# wheel_encoder.net
KiCad netlist of a schematic drawn in EAGLE
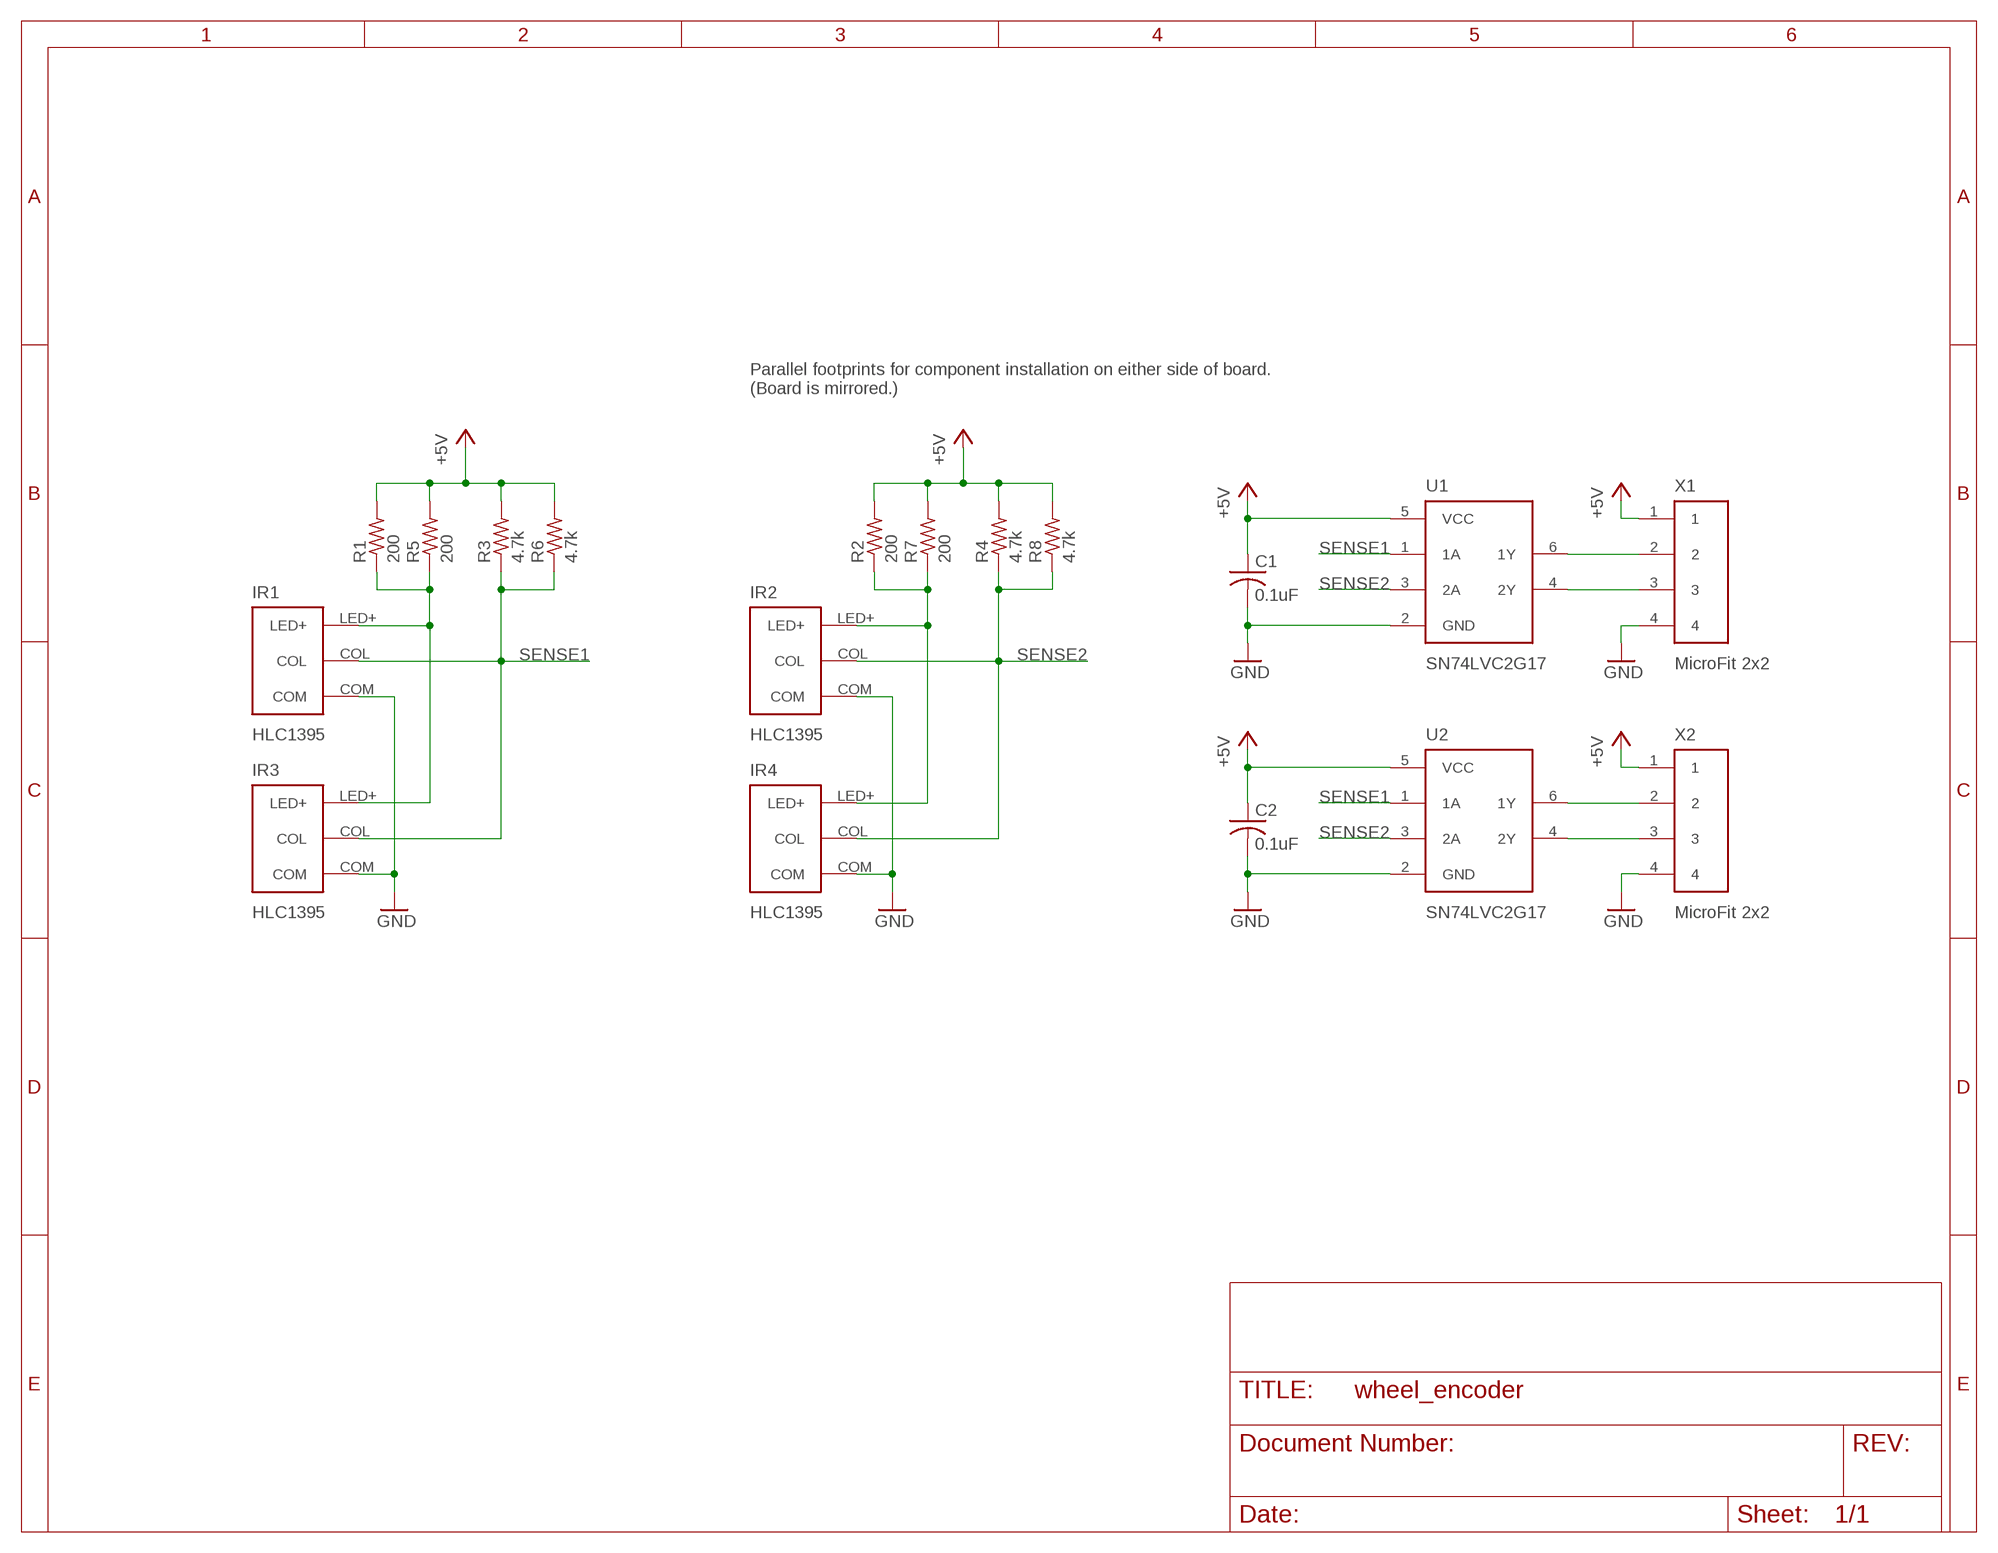
[diagram p0: schematic, sheet 1]

(export (version "E")
  (design (tool "Eeschema 10.0.6"))
  (components
    (comp (ref "C1")
      (value "0.1uF")
      (footprint "eagle-import:C0603")
      (libsource (lib "eagle-import") (part "C-USC0603"))
    )
    (comp (ref "C2")
      (value "0.1uF")
      (footprint "eagle-import:C0603")
      (libsource (lib "eagle-import") (part "C-USC0603"))
    )
    (comp (ref "IR1")
      (value "HLC1395")
      (footprint "eagle-import:HLC1395")
      (libsource (lib "eagle-import") (part "HLC1395"))
    )
    (comp (ref "IR2")
      (value "HLC1395")
      (footprint "eagle-import:HLC1395")
      (libsource (lib "eagle-import") (part "HLC1395"))
    )
    (comp (ref "IR3")
      (value "HLC1395")
      (footprint "eagle-import:HLC1395")
      (libsource (lib "eagle-import") (part "HLC1395"))
    )
    (comp (ref "IR4")
      (value "HLC1395")
      (footprint "eagle-import:HLC1395")
      (libsource (lib "eagle-import") (part "HLC1395"))
    )
    (comp (ref "R1")
      (value "200")
      (footprint "eagle-import:R0603")
      (libsource (lib "eagle-import") (part "R-US_R0603"))
    )
    (comp (ref "R2")
      (value "200")
      (footprint "eagle-import:R0603")
      (libsource (lib "eagle-import") (part "R-US_R0603"))
    )
    (comp (ref "R3")
      (value "4.7k")
      (footprint "eagle-import:R0603")
      (libsource (lib "eagle-import") (part "R-US_R0603"))
    )
    (comp (ref "R4")
      (value "4.7k")
      (footprint "eagle-import:R0603")
      (libsource (lib "eagle-import") (part "R-US_R0603"))
    )
    (comp (ref "R5")
      (value "200")
      (footprint "eagle-import:R0603")
      (libsource (lib "eagle-import") (part "R-US_R0603"))
    )
    (comp (ref "R6")
      (value "4.7k")
      (footprint "eagle-import:R0603")
      (libsource (lib "eagle-import") (part "R-US_R0603"))
    )
    (comp (ref "R7")
      (value "200")
      (footprint "eagle-import:R0603")
      (libsource (lib "eagle-import") (part "R-US_R0603"))
    )
    (comp (ref "R8")
      (value "4.7k")
      (footprint "eagle-import:R0603")
      (libsource (lib "eagle-import") (part "R-US_R0603"))
    )
    (comp (ref "U1")
      (value "SN74LVC2G17DBVR")
      (footprint "eagle-import:SOT-23-6")
      (libsource (lib "eagle-import") (part "SN74LVC2G17DBVR"))
    )
    (comp (ref "U2")
      (value "SN74LVC2G17DBVR")
      (footprint "eagle-import:SOT-23-6")
      (libsource (lib "eagle-import") (part "SN74LVC2G17DBVR"))
    )
    (comp (ref "X1")
      (value "MICROFIT-2X2-SMD")
      (footprint "eagle-import:MICROFIT-2X2-0430450411")
      (libsource (lib "eagle-import") (part "MICROFIT-2X2-SMD"))
    )
    (comp (ref "X2")
      (value "MICROFIT-2X2-SMD")
      (footprint "eagle-import:MICROFIT-2X2-0430450411")
      (libsource (lib "eagle-import") (part "MICROFIT-2X2-SMD"))
    )
  )
  (nets
    (net (code "1") (name "+5V") (class "Default")
      (node (ref "C1") (pin "1") (pinfunction "1_1") (pintype "passive"))
      (node (ref "C2") (pin "1") (pinfunction "1_1") (pintype "passive"))
      (node (ref "R1") (pin "2") (pinfunction "2_2") (pintype "passive"))
      (node (ref "R2") (pin "2") (pinfunction "2_2") (pintype "passive"))
      (node (ref "R3") (pin "2") (pinfunction "2_2") (pintype "passive"))
      (node (ref "R4") (pin "2") (pinfunction "2_2") (pintype "passive"))
      (node (ref "R5") (pin "2") (pinfunction "2_2") (pintype "passive"))
      (node (ref "R6") (pin "2") (pinfunction "2_2") (pintype "passive"))
      (node (ref "R7") (pin "2") (pinfunction "2_2") (pintype "passive"))
      (node (ref "R8") (pin "2") (pinfunction "2_2") (pintype "passive"))
      (node (ref "U1") (pin "5") (pinfunction "VCC_5") (pintype "power_in"))
      (node (ref "U2") (pin "5") (pinfunction "VCC_5") (pintype "power_in"))
      (node (ref "X1") (pin "1") (pinfunction "1_1") (pintype "bidirectional"))
      (node (ref "X2") (pin "1") (pinfunction "1_1") (pintype "bidirectional"))
    )
    (net (code "2") (name "/SENSE1") (class "Default")
      (node (ref "IR1") (pin "COL") (pinfunction "COL_COL") (pintype "input"))
      (node (ref "IR3") (pin "COL") (pinfunction "COL_COL") (pintype "input"))
      (node (ref "R3") (pin "1") (pinfunction "1_1") (pintype "passive"))
      (node (ref "R6") (pin "1") (pinfunction "1_1") (pintype "passive"))
      (node (ref "U1") (pin "1") (pinfunction "1A_1") (pintype "input"))
      (node (ref "U2") (pin "1") (pinfunction "1A_1") (pintype "input"))
    )
    (net (code "3") (name "/SENSE2") (class "Default")
      (node (ref "IR2") (pin "COL") (pinfunction "COL_COL") (pintype "input"))
      (node (ref "IR4") (pin "COL") (pinfunction "COL_COL") (pintype "input"))
      (node (ref "R4") (pin "1") (pinfunction "1_1") (pintype "passive"))
      (node (ref "R8") (pin "1") (pinfunction "1_1") (pintype "passive"))
      (node (ref "U1") (pin "3") (pinfunction "2A_3") (pintype "input"))
      (node (ref "U2") (pin "3") (pinfunction "2A_3") (pintype "input"))
    )
    (net (code "4") (name "GND") (class "Default")
      (node (ref "C1") (pin "2") (pinfunction "2_2") (pintype "passive"))
      (node (ref "C2") (pin "2") (pinfunction "2_2") (pintype "passive"))
      (node (ref "IR1") (pin "COM") (pinfunction "COM_COM") (pintype "power_in"))
      (node (ref "IR2") (pin "COM") (pinfunction "COM_COM") (pintype "power_in"))
      (node (ref "IR3") (pin "COM") (pinfunction "COM_COM") (pintype "power_in"))
      (node (ref "IR4") (pin "COM") (pinfunction "COM_COM") (pintype "power_in"))
      (node (ref "U1") (pin "2") (pinfunction "GND_2") (pintype "power_in"))
      (node (ref "U2") (pin "2") (pinfunction "GND_2") (pintype "power_in"))
      (node (ref "X1") (pin "4") (pinfunction "4_4") (pintype "bidirectional"))
      (node (ref "X2") (pin "4") (pinfunction "4_4") (pintype "bidirectional"))
    )
    (net (code "5") (name "Net-(IR1-PadLED+)") (class "Default")
      (node (ref "IR1") (pin "LED+") (pinfunction "LED+_LED+") (pintype "input"))
      (node (ref "IR3") (pin "LED+") (pinfunction "LED+_LED+") (pintype "input"))
      (node (ref "R1") (pin "1") (pinfunction "1_1") (pintype "passive"))
      (node (ref "R5") (pin "1") (pinfunction "1_1") (pintype "passive"))
    )
    (net (code "6") (name "Net-(IR2-PadLED+)") (class "Default")
      (node (ref "IR2") (pin "LED+") (pinfunction "LED+_LED+") (pintype "input"))
      (node (ref "IR4") (pin "LED+") (pinfunction "LED+_LED+") (pintype "input"))
      (node (ref "R2") (pin "1") (pinfunction "1_1") (pintype "passive"))
      (node (ref "R7") (pin "1") (pinfunction "1_1") (pintype "passive"))
    )
    (net (code "7") (name "Net-(U1-1Y)") (class "Default")
      (node (ref "U1") (pin "6") (pinfunction "1Y_6") (pintype "output"))
      (node (ref "X1") (pin "2") (pinfunction "2_2") (pintype "bidirectional"))
    )
    (net (code "8") (name "Net-(U1-2Y)") (class "Default")
      (node (ref "U1") (pin "4") (pinfunction "2Y_4") (pintype "output"))
      (node (ref "X1") (pin "3") (pinfunction "3_3") (pintype "bidirectional"))
    )
    (net (code "9") (name "Net-(U2-1Y)") (class "Default")
      (node (ref "U2") (pin "6") (pinfunction "1Y_6") (pintype "output"))
      (node (ref "X2") (pin "2") (pinfunction "2_2") (pintype "bidirectional"))
    )
    (net (code "10") (name "Net-(U2-2Y)") (class "Default")
      (node (ref "U2") (pin "4") (pinfunction "2Y_4") (pintype "output"))
      (node (ref "X2") (pin "3") (pinfunction "3_3") (pintype "bidirectional"))
    )
  )
)
